# BOOT_JTAG_AUX.net
KiCad netlist of a schematic drawn in Altium Designer
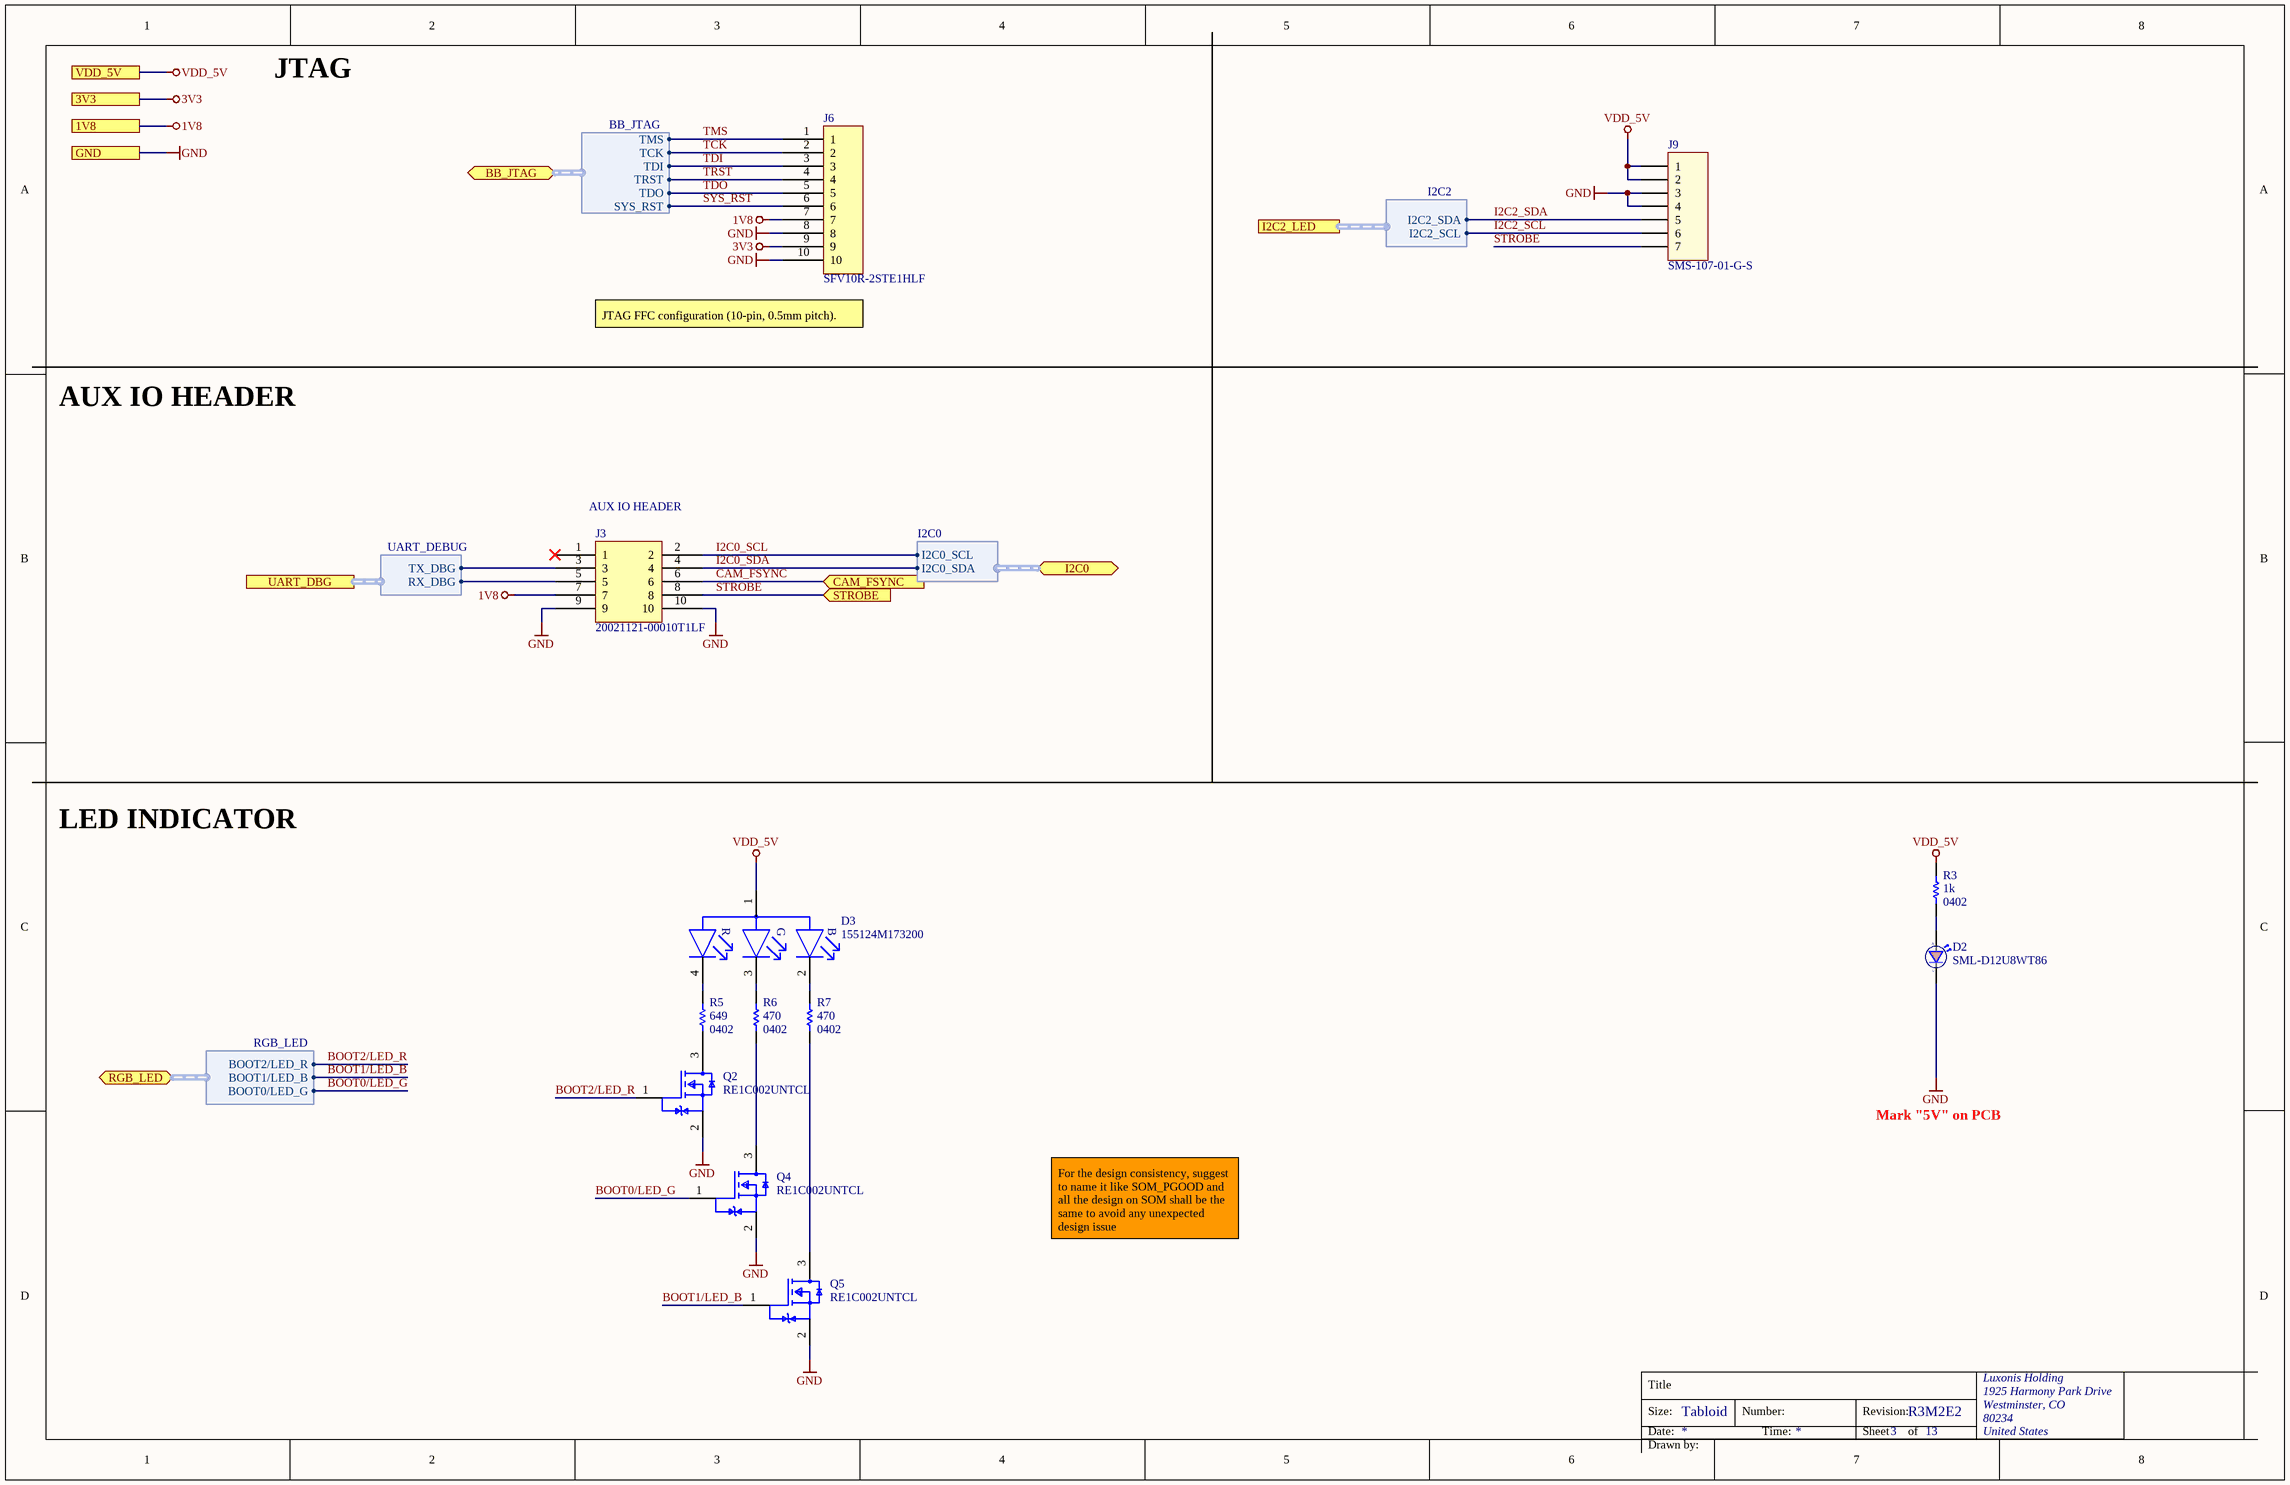
[diagram p0: BOOT_JTAG_AUX.SchDoc]

(export (version "E")
  (design (tool "Eeschema 10.0.6"))
  (components
    (comp (ref "D2")
      (value "SML-D12U8WT86")
      (footprint "SML_D1xx8W")
      (description "LED RED DIFFUSED 0603 SMD Red 620nm LED Indication - Discrete 2.2V 0603 (1608 Metric)")
      (libsource (lib "Luxonis LLC") (part "SML-D12U8WT86"))
    )
    (comp (ref "D3")
      (value "155124M173200")
      (footprint "FP-155124M173200-MFG")
      (description "Triple Color LED")
      (libsource (lib "Luxonis LLC") (part "8635049b720462866f33dfa80272b1c"))
    )
    (comp (ref "J3")
      (value "20021121-00010T1LF")
      (footprint "20021121-00010T1LF")
      (description "CONN HEADER SMD 10POS 1.27MM")
      (libsource (lib "Luxonis LLC") (part "20021121-00010T1LF"))
    )
    (comp (ref "J6")
      (value "SFV10R-2STE1HLF")
      (footprint "SFV10R-2STE1HLF")
      (description "CONN FFC TOP 10POS 0.50MM R/A")
      (libsource (lib "Luxonis LLC") (part "SFV10R-2STE1HLF"))
    )
    (comp (ref "J9")
      (value "SMS-107-01-G-S")
      (footprint "SMS-107-01-G-S")
      (libsource (lib "Luxonis LLC") (part "SMS-107-01-G-S"))
    )
    (comp (ref "Q2")
      (value "RE1C002UNTCL")
      (footprint "RE1C002UNTCL")
      (description "MOSFET N-CH 20V 0.2A EMT3")
      (libsource (lib "Luxonis LLC") (part "RE1C002UNTCL"))
    )
    (comp (ref "Q4")
      (value "RE1C002UNTCL")
      (footprint "RE1C002UNTCL")
      (description "MOSFET N-CH 20V 0.2A EMT3")
      (libsource (lib "Luxonis LLC") (part "RE1C002UNTCL"))
    )
    (comp (ref "Q5")
      (value "RE1C002UNTCL")
      (footprint "RE1C002UNTCL")
      (description "MOSFET N-CH 20V 0.2A EMT3")
      (libsource (lib "Luxonis LLC") (part "RE1C002UNTCL"))
    )
    (comp (ref "R3")
      (value "1k")
      (footprint "RESC0402(1005)_L")
      (description "RES SMD 1K OHM 1% 1/16W 0402")
      (fields
        (field (name "CASE/PACKAGE") "0402")
        (field (name "TOLERANCE") "1%")
        (field (name "Comment") "RC0402FR-071KL")
      )
      (libsource (lib "Luxonis LLC") (part "Default resistor symbol"))
    )
    (comp (ref "R5")
      (value "649")
      (footprint "RESC1005X40X25NL05T10")
      (description "RES SMD 649 OHM 1% 1/16W 0402")
      (fields
        (field (name "CASE/PACKAGE") "0402")
        (field (name "TOLERANCE") "1%")
        (field (name "Comment") "RC0402FR-07649RL")
      )
      (libsource (lib "Luxonis LLC") (part "Default resistor symbol"))
    )
    (comp (ref "R6")
      (value "470")
      (footprint "RESC0402(1005)_L")
      (description "RES SMD 470 OHM 1% 1/16W 0402")
      (fields
        (field (name "CASE/PACKAGE") "0402")
        (field (name "TOLERANCE") "1%")
        (field (name "Comment") "CRCW0402470RFKED")
      )
      (libsource (lib "Luxonis LLC") (part "Default resistor symbol"))
    )
    (comp (ref "R7")
      (value "470")
      (footprint "RESC0402(1005)_L")
      (description "RES SMD 470 OHM 1% 1/16W 0402")
      (fields
        (field (name "CASE/PACKAGE") "0402")
        (field (name "TOLERANCE") "1%")
        (field (name "Comment") "CRCW0402470RFKED")
      )
      (libsource (lib "Luxonis LLC") (part "Default resistor symbol"))
    )
  )
  (nets
    (net (code "6") (name "/BOOT0{slash}LED_G") (class "Default")
      (node (ref "Q4") (pin "1") (pinfunction "Gate_1") (pintype "passive"))
    )
    (net (code "7") (name "/BOOT1{slash}LED_B") (class "Default")
      (node (ref "Q5") (pin "1") (pinfunction "Gate_1") (pintype "passive"))
    )
    (net (code "8") (name "/BOOT2{slash}LED_R") (class "Default")
      (node (ref "Q2") (pin "1") (pinfunction "Gate_1") (pintype "passive"))
    )
    (net (code "9") (name "/CAM_FSYNC") (class "Default")
      (node (ref "J3") (pin "6") (pinfunction "6_6") (pintype "passive"))
    )
    (net (code "10") (name "/I2C0_SCL") (class "Default")
      (node (ref "J3") (pin "2") (pinfunction "2_2") (pintype "passive"))
    )
    (net (code "11") (name "/I2C0_SDA") (class "Default")
      (node (ref "J3") (pin "4") (pinfunction "4_4") (pintype "passive"))
    )
    (net (code "12") (name "/I2C2_SCL") (class "Default")
      (node (ref "J9") (pin "6") (pinfunction "6_6") (pintype "passive"))
    )
    (net (code "13") (name "/I2C2_SDA") (class "Default")
      (node (ref "J9") (pin "5") (pinfunction "5_5") (pintype "passive"))
    )
    (net (code "14") (name "/RX_DBG") (class "Default")
      (node (ref "J3") (pin "5") (pinfunction "5_5") (pintype "passive"))
    )
    (net (code "15") (name "/STROBE") (class "Default")
      (node (ref "J3") (pin "8") (pinfunction "8_8") (pintype "passive"))
      (node (ref "J9") (pin "7") (pinfunction "7_7") (pintype "passive"))
    )
    (net (code "16") (name "/SYS_RST") (class "Default")
      (node (ref "J6") (pin "6") (pinfunction "6_6") (pintype "passive"))
    )
    (net (code "17") (name "/TCK") (class "Default")
      (node (ref "J6") (pin "2") (pinfunction "2_2") (pintype "passive"))
    )
    (net (code "18") (name "/TDI") (class "Default")
      (node (ref "J6") (pin "3") (pinfunction "3_3") (pintype "passive"))
    )
    (net (code "19") (name "/TDO") (class "Default")
      (node (ref "J6") (pin "5") (pinfunction "5_5") (pintype "passive"))
    )
    (net (code "20") (name "/TMS") (class "Default")
      (node (ref "J6") (pin "1") (pinfunction "1_1") (pintype "passive"))
    )
    (net (code "21") (name "/TRST") (class "Default")
      (node (ref "J6") (pin "4") (pinfunction "4_4") (pintype "passive"))
    )
    (net (code "22") (name "/TX_DBG") (class "Default")
      (node (ref "J3") (pin "3") (pinfunction "3_3") (pintype "passive"))
    )
    (net (code "28") (name "1V8") (class "Default")
      (node (ref "J3") (pin "7") (pinfunction "7_7") (pintype "passive"))
      (node (ref "J6") (pin "7") (pinfunction "7_7") (pintype "passive"))
    )
    (net (code "29") (name "3V3") (class "Default")
      (node (ref "J6") (pin "9") (pinfunction "9_9") (pintype "passive"))
    )
    (net (code "30") (name "GND") (class "Default")
      (node (ref "D2") (pin "1") (pinfunction "C_1") (pintype "passive"))
      (node (ref "J3") (pin "10") (pinfunction "10_10") (pintype "passive"))
      (node (ref "J3") (pin "9") (pinfunction "9_9") (pintype "passive"))
      (node (ref "J6") (pin "10") (pinfunction "10_10") (pintype "passive"))
      (node (ref "J6") (pin "8") (pinfunction "8_8") (pintype "passive"))
      (node (ref "J9") (pin "3") (pinfunction "3_3") (pintype "passive"))
      (node (ref "J9") (pin "4") (pinfunction "4_4") (pintype "passive"))
      (node (ref "Q2") (pin "2") (pinfunction "Source_2") (pintype "passive"))
      (node (ref "Q4") (pin "2") (pinfunction "Source_2") (pintype "passive"))
      (node (ref "Q5") (pin "2") (pinfunction "Source_2") (pintype "passive"))
    )
    (net (code "31") (name "Net-(D2-A)") (class "Default")
      (node (ref "D2") (pin "2") (pinfunction "A_2") (pintype "passive"))
      (node (ref "R3") (pin "1") (pinfunction "1_1") (pintype "passive"))
    )
    (net (code "32") (name "Net-(D3-BLUE_C)") (class "Default")
      (node (ref "D3") (pin "2") (pinfunction "BLUE_C_2") (pintype "passive"))
      (node (ref "R7") (pin "2") (pinfunction "2_2") (pintype "passive"))
    )
    (net (code "33") (name "Net-(D3-GREEN_C)") (class "Default")
      (node (ref "D3") (pin "3") (pinfunction "GREEN_C_3") (pintype "passive"))
      (node (ref "R6") (pin "2") (pinfunction "2_2") (pintype "passive"))
    )
    (net (code "34") (name "Net-(D3-RED_C)") (class "Default")
      (node (ref "D3") (pin "4") (pinfunction "RED_C_4") (pintype "passive"))
      (node (ref "R5") (pin "2") (pinfunction "2_2") (pintype "passive"))
    )
    (net (code "35") (name "Net-(Q2-Drain)") (class "Default")
      (node (ref "Q2") (pin "3") (pinfunction "Drain_3") (pintype "passive"))
      (node (ref "R5") (pin "1") (pinfunction "1_1") (pintype "passive"))
    )
    (net (code "36") (name "Net-(Q4-Drain)") (class "Default")
      (node (ref "Q4") (pin "3") (pinfunction "Drain_3") (pintype "passive"))
      (node (ref "R6") (pin "1") (pinfunction "1_1") (pintype "passive"))
    )
    (net (code "37") (name "Net-(Q5-Drain)") (class "Default")
      (node (ref "Q5") (pin "3") (pinfunction "Drain_3") (pintype "passive"))
      (node (ref "R7") (pin "1") (pinfunction "1_1") (pintype "passive"))
    )
    (net (code "38") (name "VDD_5V") (class "Default")
      (node (ref "D3") (pin "1") (pinfunction "COMMON_ANODE_1") (pintype "passive"))
      (node (ref "J9") (pin "1") (pinfunction "1_1") (pintype "passive"))
      (node (ref "J9") (pin "2") (pinfunction "2_2") (pintype "passive"))
      (node (ref "R3") (pin "2") (pinfunction "2_2") (pintype "passive"))
    )
    (net (code "39") (name "unconnected-(J3-Pad1)") (class "Default")
      (node (ref "J3") (pin "1") (pinfunction "1_1") (pintype "passive+no_connect"))
    )
  )
)
